# DASH_CONNECTORS.net
KiCad netlist of a schematic drawn in Altium Designer
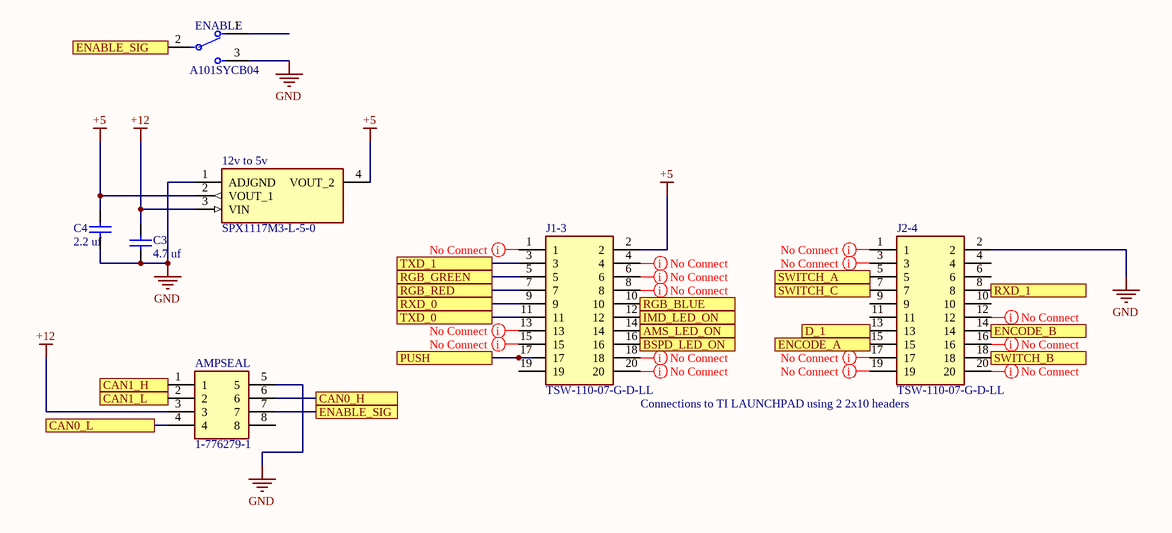
[diagram p0: DASH_CONNECTORS.SchDoc]

(export (version "E")
  (design (tool "Eeschema 10.0.6"))
  (components
    (comp (ref "12v to 5v")
      (value "SPX1117M3-L-5-0")
      (footprint "SamacSys:SOT230P700X170-4N")
      (description "Power Supply")
      (fields (field (name "MOUSER PART NUMBER") "701-SPX1117M3-L-5-0"))
      (libsource (lib "*") (part "SPX1117M3-L-5-0"))
    )
    (comp (ref "AMPSEAL")
      (value "1-776279-1")
      (footprint "SamacSys:17762791")
      (description "Connector")
      (fields (field (name "MOUSER PART NUMBER") "571-1-776279-1"))
      (libsource (lib "*") (part "1-776279-1"))
    )
    (comp (ref "C3")
      (value "4.7 uf")
      (footprint "CAPC1608X87X35NL15T15")
      (description ".1 uf")
      (fields (field (name "PART NUMBER") "C0603C104J3RAC7867") (field (name "MANUFACTURER") "Kemet"))
      (libsource (lib "Altium Content Vault") (part "CAP"))
    )
    (comp (ref "C4")
      (value "2.2 uf")
      (footprint "CAPC1608X87X35NL15T15")
      (description ".1 uf")
      (fields (field (name "PART NUMBER") "C0603C104J3RAC7867") (field (name "MANUFACTURER") "Kemet"))
      (libsource (lib "Altium Content Vault") (part "CAP"))
    )
    (comp (ref "ENABLE")
      (value "A101SYCB04")
      (footprint "FP-A101SYCB04-MFG")
      (description "SWITCH TOGGLE SPDT 0.4VA 20V")
      (libsource (lib "Altium Content Vault") (part "52c419afdc2a387c7d548259a9aeefb"))
    )
    (comp (ref "J1-3")
      (value "TSW-110-07-G-D-LL")
      (footprint "SamacSys:HDRV20W64P254_2X10_2540X495X838P")
      (description "Connector")
      (fields (field (name "MOUSER PART NUMBER") "200-TSW11007GDLL"))
      (libsource (lib "*") (part "TSW-110-07-G-D-LL"))
    )
    (comp (ref "J2-4")
      (value "TSW-110-07-G-D-LL")
      (footprint "SamacSys:HDRV20W64P254_2X10_2540X495X838P")
      (description "Connector")
      (fields (field (name "MOUSER PART NUMBER") "200-TSW11007GDLL"))
      (libsource (lib "*") (part "TSW-110-07-G-D-LL"))
    )
  )
  (nets
    (net (code "1") (name "+5") (class "Default")
      (node (ref "12v to 5v") (pin "2") (pinfunction "VOUT_1_2") (pintype "output"))
      (node (ref "12v to 5v") (pin "4") (pinfunction "VOUT_2_4") (pintype "passive"))
      (node (ref "C4") (pin "2") (pinfunction "2_2") (pintype "passive"))
      (node (ref "J1-3") (pin "2") (pinfunction "2_2") (pintype "passive"))
    )
    (net (code "2") (name "+12") (class "Default")
      (node (ref "12v to 5v") (pin "3") (pinfunction "VIN_3") (pintype "input"))
      (node (ref "AMPSEAL") (pin "3") (pinfunction "3_3") (pintype "passive"))
      (node (ref "C3") (pin "2") (pinfunction "2_2") (pintype "passive"))
    )
    (net (code "3") (name "/AMS_LED_ON") (class "Default")
      (node (ref "J1-3") (pin "14") (pinfunction "14_14") (pintype "passive"))
    )
    (net (code "4") (name "/BSPD_LED_ON") (class "Default")
      (node (ref "J1-3") (pin "16") (pinfunction "16_16") (pintype "passive"))
    )
    (net (code "5") (name "/CAN0_H") (class "Default")
      (node (ref "AMPSEAL") (pin "6") (pinfunction "6_6") (pintype "passive"))
    )
    (net (code "6") (name "/CAN0_L") (class "Default")
      (node (ref "AMPSEAL") (pin "4") (pinfunction "4_4") (pintype "passive"))
    )
    (net (code "7") (name "/CAN1_H") (class "Default")
      (node (ref "AMPSEAL") (pin "1") (pinfunction "1_1") (pintype "passive"))
    )
    (net (code "8") (name "/CAN1_L") (class "Default")
      (node (ref "AMPSEAL") (pin "2") (pinfunction "2_2") (pintype "passive"))
    )
    (net (code "9") (name "/D_1") (class "Default")
      (node (ref "J2-4") (pin "13") (pinfunction "13_13") (pintype "passive"))
    )
    (net (code "10") (name "/ENABLE_SIG") (class "Default")
      (node (ref "AMPSEAL") (pin "7") (pinfunction "7_7") (pintype "passive"))
      (node (ref "ENABLE") (pin "2") (pinfunction "2_2") (pintype "passive"))
    )
    (net (code "11") (name "/ENCODE_A") (class "Default")
      (node (ref "J2-4") (pin "15") (pinfunction "15_15") (pintype "passive"))
    )
    (net (code "12") (name "/ENCODE_B") (class "Default")
      (node (ref "J2-4") (pin "14") (pinfunction "14_14") (pintype "passive"))
    )
    (net (code "13") (name "/IMD_LED_ON") (class "Default")
      (node (ref "J1-3") (pin "12") (pinfunction "12_12") (pintype "passive"))
    )
    (net (code "14") (name "/PUSH") (class "Default")
      (node (ref "J1-3") (pin "17") (pinfunction "17_17") (pintype "passive"))
    )
    (net (code "15") (name "/RGB_BLUE") (class "Default")
      (node (ref "J1-3") (pin "10") (pinfunction "10_10") (pintype "passive"))
    )
    (net (code "16") (name "/RGB_GREEN") (class "Default")
      (node (ref "J1-3") (pin "5") (pinfunction "5_5") (pintype "passive"))
    )
    (net (code "17") (name "/RGB_RED") (class "Default")
      (node (ref "J1-3") (pin "7") (pinfunction "7_7") (pintype "passive"))
    )
    (net (code "18") (name "/RXD_0") (class "Default")
      (node (ref "J1-3") (pin "9") (pinfunction "9_9") (pintype "passive"))
    )
    (net (code "19") (name "/RXD_1") (class "Default")
      (node (ref "J2-4") (pin "8") (pinfunction "8_8") (pintype "passive"))
    )
    (net (code "20") (name "/SWITCH_A") (class "Default")
      (node (ref "J2-4") (pin "5") (pinfunction "5_5") (pintype "passive"))
    )
    (net (code "21") (name "/SWITCH_B") (class "Default")
      (node (ref "J2-4") (pin "18") (pinfunction "18_18") (pintype "passive"))
    )
    (net (code "22") (name "/SWITCH_C") (class "Default")
      (node (ref "J2-4") (pin "7") (pinfunction "7_7") (pintype "passive"))
    )
    (net (code "23") (name "/TXD_0") (class "Default")
      (node (ref "J1-3") (pin "11") (pinfunction "11_11") (pintype "passive"))
    )
    (net (code "24") (name "/TXD_1") (class "Default")
      (node (ref "J1-3") (pin "3") (pinfunction "3_3") (pintype "passive"))
    )
    (net (code "25") (name "GND") (class "Default")
      (node (ref "12v to 5v") (pin "1") (pinfunction "ADJGND_1") (pintype "power_in"))
      (node (ref "AMPSEAL") (pin "5") (pinfunction "5_5") (pintype "passive"))
      (node (ref "C3") (pin "1") (pinfunction "1_1") (pintype "passive"))
      (node (ref "C4") (pin "1") (pinfunction "1_1") (pintype "passive"))
      (node (ref "ENABLE") (pin "3") (pinfunction "3_3") (pintype "passive"))
      (node (ref "J2-4") (pin "2") (pinfunction "2_2") (pintype "passive"))
    )
    (net (code "26") (name "unconnected-(AMPSEAL-Pad8)") (class "Default")
      (node (ref "AMPSEAL") (pin "8") (pinfunction "8_8") (pintype "passive"))
    )
    (net (code "27") (name "unconnected-(ENABLE-Pad1)") (class "Default")
      (node (ref "ENABLE") (pin "1") (pinfunction "1_1") (pintype "passive"))
    )
    (net (code "28") (name "unconnected-(J1-3-Pad1)") (class "Default")
      (node (ref "J1-3") (pin "1") (pinfunction "1_1") (pintype "passive"))
    )
    (net (code "29") (name "unconnected-(J1-3-Pad4)") (class "Default")
      (node (ref "J1-3") (pin "4") (pinfunction "4_4") (pintype "passive"))
    )
    (net (code "30") (name "unconnected-(J1-3-Pad6)") (class "Default")
      (node (ref "J1-3") (pin "6") (pinfunction "6_6") (pintype "passive"))
    )
    (net (code "31") (name "unconnected-(J1-3-Pad8)") (class "Default")
      (node (ref "J1-3") (pin "8") (pinfunction "8_8") (pintype "passive"))
    )
    (net (code "32") (name "unconnected-(J1-3-Pad13)") (class "Default")
      (node (ref "J1-3") (pin "13") (pinfunction "13_13") (pintype "passive"))
    )
    (net (code "33") (name "unconnected-(J1-3-Pad15)") (class "Default")
      (node (ref "J1-3") (pin "15") (pinfunction "15_15") (pintype "passive"))
    )
    (net (code "34") (name "unconnected-(J1-3-Pad18)") (class "Default")
      (node (ref "J1-3") (pin "18") (pinfunction "18_18") (pintype "passive"))
    )
    (net (code "35") (name "unconnected-(J1-3-Pad19)") (class "Default")
      (node (ref "J1-3") (pin "19") (pinfunction "19_19") (pintype "passive"))
    )
    (net (code "36") (name "unconnected-(J1-3-Pad20)") (class "Default")
      (node (ref "J1-3") (pin "20") (pinfunction "20_20") (pintype "passive"))
    )
    (net (code "37") (name "unconnected-(J2-4-Pad1)") (class "Default")
      (node (ref "J2-4") (pin "1") (pinfunction "1_1") (pintype "passive"))
    )
    (net (code "38") (name "unconnected-(J2-4-Pad3)") (class "Default")
      (node (ref "J2-4") (pin "3") (pinfunction "3_3") (pintype "passive"))
    )
    (net (code "39") (name "unconnected-(J2-4-Pad4)") (class "Default")
      (node (ref "J2-4") (pin "4") (pinfunction "4_4") (pintype "passive"))
    )
    (net (code "40") (name "unconnected-(J2-4-Pad6)") (class "Default")
      (node (ref "J2-4") (pin "6") (pinfunction "6_6") (pintype "passive"))
    )
    (net (code "41") (name "unconnected-(J2-4-Pad9)") (class "Default")
      (node (ref "J2-4") (pin "9") (pinfunction "9_9") (pintype "passive"))
    )
    (net (code "42") (name "unconnected-(J2-4-Pad10)") (class "Default")
      (node (ref "J2-4") (pin "10") (pinfunction "10_10") (pintype "passive"))
    )
    (net (code "43") (name "unconnected-(J2-4-Pad11)") (class "Default")
      (node (ref "J2-4") (pin "11") (pinfunction "11_11") (pintype "passive"))
    )
    (net (code "44") (name "unconnected-(J2-4-Pad12)") (class "Default")
      (node (ref "J2-4") (pin "12") (pinfunction "12_12") (pintype "passive"))
    )
    (net (code "45") (name "unconnected-(J2-4-Pad16)") (class "Default")
      (node (ref "J2-4") (pin "16") (pinfunction "16_16") (pintype "passive"))
    )
    (net (code "46") (name "unconnected-(J2-4-Pad17)") (class "Default")
      (node (ref "J2-4") (pin "17") (pinfunction "17_17") (pintype "passive"))
    )
    (net (code "47") (name "unconnected-(J2-4-Pad19)") (class "Default")
      (node (ref "J2-4") (pin "19") (pinfunction "19_19") (pintype "passive"))
    )
    (net (code "48") (name "unconnected-(J2-4-Pad20)") (class "Default")
      (node (ref "J2-4") (pin "20") (pinfunction "20_20") (pintype "passive"))
    )
  )
)
